# pwr_supply.net
KiCad netlist of a schematic drawn in Altium Designer
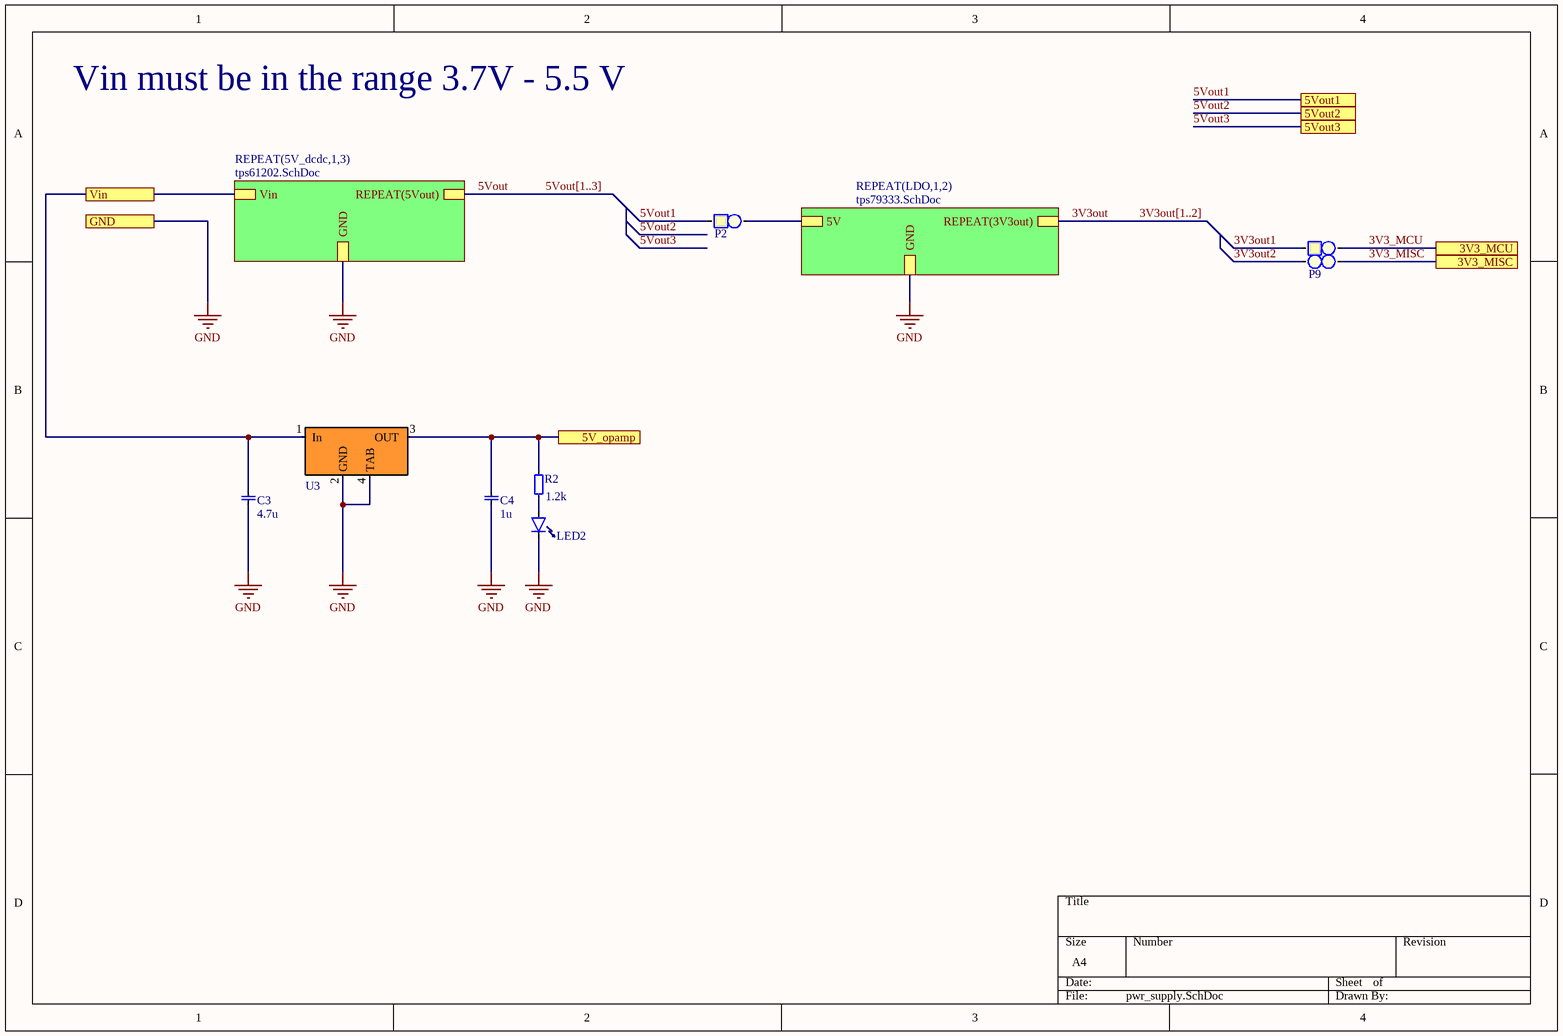
[diagram p0: pwr_supply.SchDoc]

(export (version "E")
  (design (tool "Eeschema 10.0.6"))
  (components
    (comp (ref "C3")
      (value "4.7u")
      (footprint "1206, capasitor")
      (fields (field (name "Comment") "1206, capacitor"))
      (libsource (lib "eitp15_lab1_lib") (part "1206, capacitor"))
    )
    (comp (ref "C4")
      (value "1u")
      (footprint "1206, capasitor")
      (fields (field (name "Comment") "1206, capacitor"))
      (libsource (lib "eitp15_lab1_lib") (part "1206, capacitor"))
    )
    (comp (ref "LED2")
      (value "0805, LED")
      (footprint "0805_led")
      (libsource (lib "eitp15_lab1_lib") (part "0805, LED"))
    )
    (comp (ref "P2")
      (value "Jumper")
      (footprint "padtwo_L")
      (description "2.54 mm, TH")
      (libsource (lib "jclib") (part "Jumper"))
    )
    (comp (ref "P9")
      (value "2x2 Pin Header")
      (footprint "2x2 PH")
      (libsource (lib "jclib") (part "2x2 Pin Header"))
    )
    (comp (ref "R2")
      (value "1.2k")
      (footprint "1206")
      (description "Resistor")
      (fields (field (name "Comment") "1206, resistor"))
      (libsource (lib "eitp15_lab1_lib") (part "1206, resistor"))
    )
    (comp (ref "U3")
      (value "MCP1826S")
      (footprint "SOT223")
      (description "Max input voltage is 6.0 V, tab connects to ground")
      (libsource (lib "jclib") (part "MCP1826S"))
    )
  )
  (nets
    (net (code "1") (name "/3V3_MCU") (class "Default")
      (node (ref "P9") (pin "4") (pinfunction "4_4") (pintype "passive"))
    )
    (net (code "2") (name "/3V3_MISC") (class "Default")
      (node (ref "P9") (pin "3") (pinfunction "3_3") (pintype "passive"))
    )
    (net (code "4") (name "/3V3out1") (class "Default")
      (node (ref "P9") (pin "1") (pinfunction "1_1") (pintype "passive"))
    )
    (net (code "5") (name "/3V3out2") (class "Default")
      (node (ref "P9") (pin "2") (pinfunction "2_2") (pintype "passive"))
    )
    (net (code "7") (name "/5V") (class "Default")
      (node (ref "P2") (pin "2") (pinfunction "2_2") (pintype "passive"))
    )
    (net (code "8") (name "/5V_opamp") (class "Default")
      (node (ref "C4") (pin "1") (pinfunction "1_1") (pintype "passive"))
      (node (ref "R2") (pin "0") (pinfunction "0_0") (pintype "passive"))
      (node (ref "U3") (pin "3") (pinfunction "OUT_3") (pintype "passive"))
    )
    (net (code "10") (name "/5Vout1") (class "Default")
      (node (ref "P2") (pin "1") (pinfunction "1_1") (pintype "passive"))
    )
    (net (code "14") (name "/Vin") (class "Default")
      (node (ref "C3") (pin "1") (pinfunction "1_1") (pintype "passive"))
      (node (ref "U3") (pin "1") (pinfunction "In_1") (pintype "passive"))
    )
    (net (code "15") (name "GND") (class "Default")
      (node (ref "C3") (pin "0") (pinfunction "0_0") (pintype "passive"))
      (node (ref "C4") (pin "0") (pinfunction "0_0") (pintype "passive"))
      (node (ref "LED2") (pin "0") (pinfunction "Cathode_0") (pintype "passive"))
      (node (ref "U3") (pin "2") (pinfunction "GND_2") (pintype "passive"))
      (node (ref "U3") (pin "4") (pinfunction "TAB_4") (pintype "passive"))
    )
    (net (code "16") (name "Net-(LED2-Pad1)") (class "Default")
      (node (ref "LED2") (pin "1") (pinfunction "1_1") (pintype "passive"))
      (node (ref "R2") (pin "1") (pinfunction "1_1") (pintype "passive"))
    )
  )
)
